# DCDC-12V5V1A.net
KiCad netlist of a schematic drawn in EAGLE
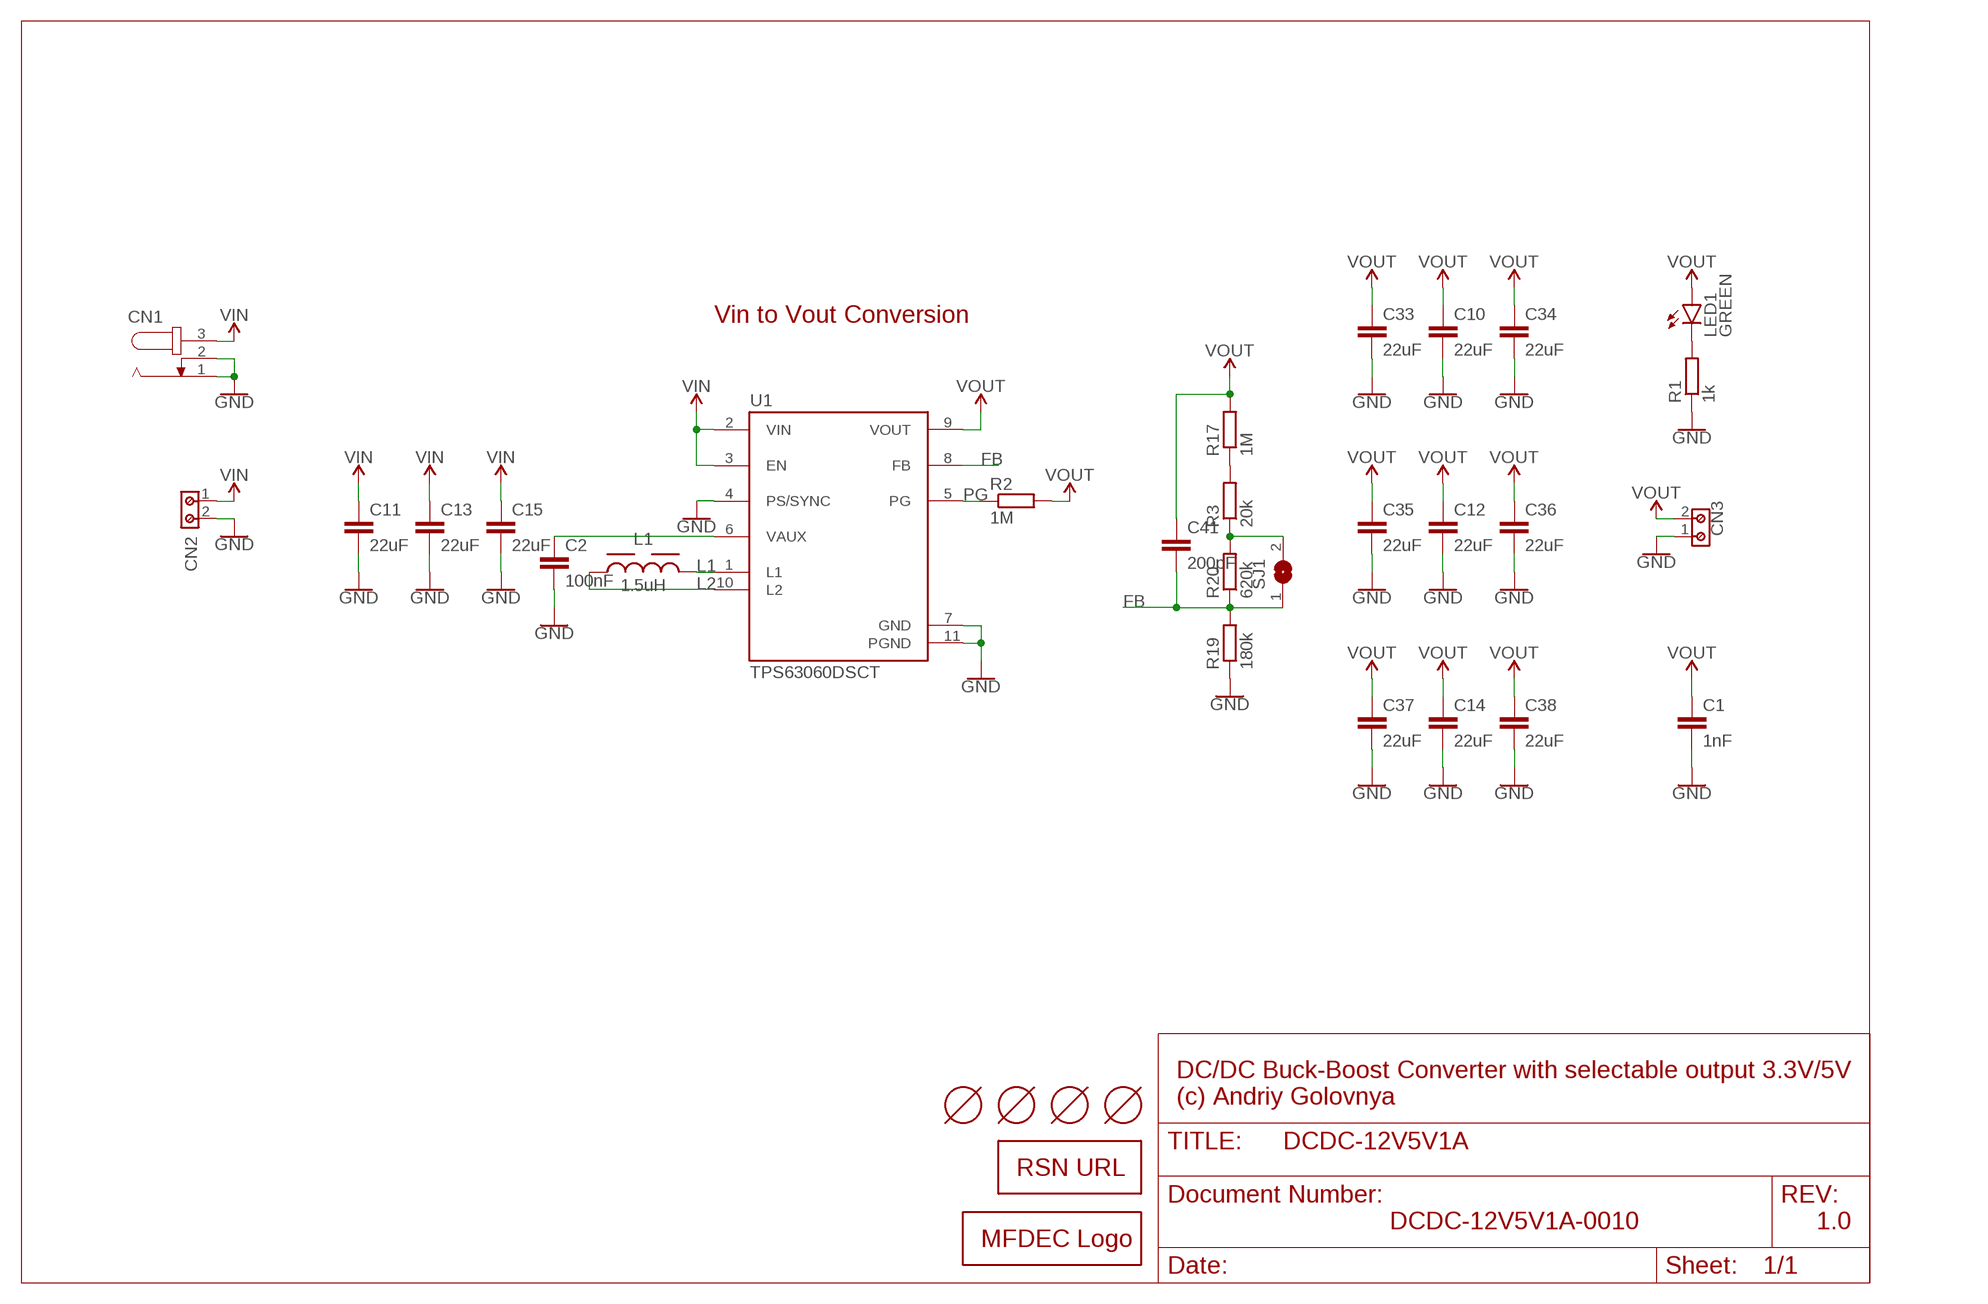
[diagram p0: schematic, sheet 1]

(export (version "E")
  (design (tool "Eeschema 10.0.6"))
  (components
    (comp (ref "C1")
      (value "1nF")
      (footprint "eagle-import:C0603K")
      (libsource (lib "eagle-import") (part "C-EUC0603K"))
    )
    (comp (ref "C2")
      (value "100nF")
      (footprint "eagle-import:C0603K")
      (libsource (lib "eagle-import") (part "C-EUC0603K"))
    )
    (comp (ref "C10")
      (value "22uF")
      (footprint "eagle-import:C0805K")
      (libsource (lib "eagle-import") (part "C-EUC0805K"))
    )
    (comp (ref "C11")
      (value "22uF")
      (footprint "eagle-import:C0805K")
      (libsource (lib "eagle-import") (part "C-EUC0805K"))
    )
    (comp (ref "C12")
      (value "22uF")
      (footprint "eagle-import:C0805K")
      (libsource (lib "eagle-import") (part "C-EUC0805K"))
    )
    (comp (ref "C13")
      (value "22uF")
      (footprint "eagle-import:C0805K")
      (libsource (lib "eagle-import") (part "C-EUC0805K"))
    )
    (comp (ref "C14")
      (value "22uF")
      (footprint "eagle-import:C0805K")
      (libsource (lib "eagle-import") (part "C-EUC0805K"))
    )
    (comp (ref "C15")
      (value "22uF")
      (footprint "eagle-import:C0805K")
      (libsource (lib "eagle-import") (part "C-EUC0805K"))
    )
    (comp (ref "C33")
      (value "22uF")
      (footprint "eagle-import:C0805K")
      (libsource (lib "eagle-import") (part "C-EUC0805K"))
    )
    (comp (ref "C34")
      (value "22uF")
      (footprint "eagle-import:C0805K")
      (libsource (lib "eagle-import") (part "C-EUC0805K"))
    )
    (comp (ref "C35")
      (value "22uF")
      (footprint "eagle-import:C0805K")
      (libsource (lib "eagle-import") (part "C-EUC0805K"))
    )
    (comp (ref "C36")
      (value "22uF")
      (footprint "eagle-import:C0805K")
      (libsource (lib "eagle-import") (part "C-EUC0805K"))
    )
    (comp (ref "C37")
      (value "22uF")
      (footprint "eagle-import:C0805K")
      (libsource (lib "eagle-import") (part "C-EUC0805K"))
    )
    (comp (ref "C38")
      (value "22uF")
      (footprint "eagle-import:C0805K")
      (libsource (lib "eagle-import") (part "C-EUC0805K"))
    )
    (comp (ref "C41")
      (value "200pF")
      (footprint "eagle-import:C0603K")
      (libsource (lib "eagle-import") (part "C-EUC0603K"))
    )
    (comp (ref "CN1")
      (value "JACK-PLUG1")
      (footprint "eagle-import:SPC4078")
      (libsource (lib "eagle-import") (part "JACK-PLUG1"))
    )
    (comp (ref "CN2")
      (value "691213510002")
      (footprint "eagle-import:691213510002")
      (libsource (lib "eagle-import") (part "691213510002"))
    )
    (comp (ref "CN3")
      (value "691213510002")
      (footprint "eagle-import:691213510002")
      (libsource (lib "eagle-import") (part "691213510002"))
    )
    (comp (ref "HOLE1")
      (value "TOOLINGHOLE")
      (footprint "eagle-import:TOOLING-HOLE")
      (libsource (lib "eagle-import") (part "TOOLINGHOLE"))
    )
    (comp (ref "HOLE2")
      (value "TOOLINGHOLE")
      (footprint "eagle-import:TOOLING-HOLE")
      (libsource (lib "eagle-import") (part "TOOLINGHOLE"))
    )
    (comp (ref "HOLE3")
      (value "TOOLINGHOLE")
      (footprint "eagle-import:TOOLING-HOLE")
      (libsource (lib "eagle-import") (part "TOOLINGHOLE"))
    )
    (comp (ref "HOLE4")
      (value "TOOLINGHOLE")
      (footprint "eagle-import:TOOLING-HOLE")
      (libsource (lib "eagle-import") (part "TOOLINGHOLE"))
    )
    (comp (ref "L1")
      (value "1.5uH")
      (footprint "eagle-import:WE-LQS_4018")
      (libsource (lib "eagle-import") (part "WE-LQS_4018_74404042010"))
    )
    (comp (ref "LED1")
      (value "GREEN")
      (footprint "eagle-import:SML0603")
      (libsource (lib "eagle-import") (part "LEDSML0603"))
    )
    (comp (ref "LOGO1")
      (value "RSNURL_QR_8MM")
      (footprint "eagle-import:RSNURL_QR_8MM")
      (libsource (lib "eagle-import") (part "RSNURL_QR_8MM"))
    )
    (comp (ref "LOGO2")
      (value "MFDECLOGO_L_10MM")
      (footprint "eagle-import:MFDEC_L_10MM")
      (libsource (lib "eagle-import") (part "MFDECLOGO_L_10MM"))
    )
    (comp (ref "R1")
      (value "1k")
      (footprint "eagle-import:R0603")
      (libsource (lib "eagle-import") (part "R-EU_R0603"))
    )
    (comp (ref "R2")
      (value "1M")
      (footprint "eagle-import:R0603")
      (libsource (lib "eagle-import") (part "R-EU_R0603"))
    )
    (comp (ref "R3")
      (value "20k")
      (footprint "eagle-import:R0603")
      (libsource (lib "eagle-import") (part "R-EU_R0603"))
    )
    (comp (ref "R17")
      (value "1M")
      (footprint "eagle-import:R0603")
      (libsource (lib "eagle-import") (part "R-EU_R0603"))
    )
    (comp (ref "R19")
      (value "180k")
      (footprint "eagle-import:R0603")
      (libsource (lib "eagle-import") (part "R-EU_R0603"))
    )
    (comp (ref "R20")
      (value "620k")
      (footprint "eagle-import:R0603")
      (libsource (lib "eagle-import") (part "R-EU_R0603"))
    )
    (comp (ref "SJ1") (value "SJ") (footprint "eagle-import:SJ") (libsource (lib "eagle-import") (part "SJ")))
    (comp (ref "U1")
      (value "TPS63060DSCT")
      (footprint "eagle-import:CONV_TPS63060DSCT")
      (fields (field (name "MF") "Texas Instruments"))
      (libsource (lib "eagle-import") (part "TPS63060DSCT"))
    )
  )
  (nets
    (net (code "1") (name "/FB") (class "Default")
      (node (ref "C41") (pin "2") (pinfunction "2_2") (pintype "passive"))
      (node (ref "R19") (pin "2") (pinfunction "2_2") (pintype "passive"))
      (node (ref "R20") (pin "1") (pinfunction "1_1") (pintype "passive"))
      (node (ref "SJ1") (pin "1") (pinfunction "1_1") (pintype "passive"))
      (node (ref "U1") (pin "8") (pinfunction "FB_8") (pintype "input"))
    )
    (net (code "2") (name "/L1") (class "Default")
      (node (ref "L1") (pin "2") (pinfunction "2_2") (pintype "passive"))
      (node (ref "U1") (pin "1") (pinfunction "L1_1") (pintype "passive"))
    )
    (net (code "3") (name "/L2") (class "Default")
      (node (ref "L1") (pin "1") (pinfunction "1_1") (pintype "passive"))
      (node (ref "U1") (pin "10") (pinfunction "L2_10") (pintype "passive"))
    )
    (net (code "4") (name "/PG") (class "Default")
      (node (ref "R2") (pin "1") (pinfunction "1_1") (pintype "passive"))
      (node (ref "U1") (pin "5") (pinfunction "PG_5") (pintype "output"))
    )
    (net (code "5") (name "GND") (class "Default")
      (node (ref "C1") (pin "2") (pinfunction "2_2") (pintype "passive"))
      (node (ref "C10") (pin "2") (pinfunction "2_2") (pintype "passive"))
      (node (ref "C11") (pin "2") (pinfunction "2_2") (pintype "passive"))
      (node (ref "C12") (pin "2") (pinfunction "2_2") (pintype "passive"))
      (node (ref "C13") (pin "2") (pinfunction "2_2") (pintype "passive"))
      (node (ref "C14") (pin "2") (pinfunction "2_2") (pintype "passive"))
      (node (ref "C15") (pin "2") (pinfunction "2_2") (pintype "passive"))
      (node (ref "C2") (pin "2") (pinfunction "2_2") (pintype "passive"))
      (node (ref "C33") (pin "2") (pinfunction "2_2") (pintype "passive"))
      (node (ref "C34") (pin "2") (pinfunction "2_2") (pintype "passive"))
      (node (ref "C35") (pin "2") (pinfunction "2_2") (pintype "passive"))
      (node (ref "C36") (pin "2") (pinfunction "2_2") (pintype "passive"))
      (node (ref "C37") (pin "2") (pinfunction "2_2") (pintype "passive"))
      (node (ref "C38") (pin "2") (pinfunction "2_2") (pintype "passive"))
      (node (ref "CN1") (pin "1") (pinfunction "1_1") (pintype "passive"))
      (node (ref "CN1") (pin "2") (pinfunction "2_2") (pintype "passive"))
      (node (ref "CN2") (pin "2") (pinfunction "2_2") (pintype "passive"))
      (node (ref "CN3") (pin "1") (pinfunction "1_1") (pintype "passive"))
      (node (ref "R1") (pin "1") (pinfunction "1_1") (pintype "passive"))
      (node (ref "R19") (pin "1") (pinfunction "1_1") (pintype "passive"))
      (node (ref "U1") (pin "11") (pinfunction "PGND_11") (pintype "power_in"))
      (node (ref "U1") (pin "4") (pinfunction "PS/SYNC_4") (pintype "input"))
      (node (ref "U1") (pin "7") (pinfunction "GND_7") (pintype "power_in"))
    )
    (net (code "6") (name "Net-(LED1-PadC)") (class "Default")
      (node (ref "LED1") (pin "C") (pinfunction "C_C") (pintype "passive"))
      (node (ref "R1") (pin "2") (pinfunction "2_2") (pintype "passive"))
    )
    (net (code "7") (name "Net-(R17-Pad1)") (class "Default")
      (node (ref "R17") (pin "1") (pinfunction "1_1") (pintype "passive"))
      (node (ref "R3") (pin "2") (pinfunction "2_2") (pintype "passive"))
    )
    (net (code "8") (name "Net-(R20-Pad2)") (class "Default")
      (node (ref "R20") (pin "2") (pinfunction "2_2") (pintype "passive"))
      (node (ref "R3") (pin "1") (pinfunction "1_1") (pintype "passive"))
      (node (ref "SJ1") (pin "2") (pinfunction "2_2") (pintype "passive"))
    )
    (net (code "9") (name "Net-(U1-VAUX)") (class "Default")
      (node (ref "C2") (pin "1") (pinfunction "1_1") (pintype "passive"))
      (node (ref "U1") (pin "6") (pinfunction "VAUX_6") (pintype "passive"))
    )
    (net (code "10") (name "VIN") (class "Default")
      (node (ref "C11") (pin "1") (pinfunction "1_1") (pintype "passive"))
      (node (ref "C13") (pin "1") (pinfunction "1_1") (pintype "passive"))
      (node (ref "C15") (pin "1") (pinfunction "1_1") (pintype "passive"))
      (node (ref "CN1") (pin "3") (pinfunction "3_3") (pintype "passive"))
      (node (ref "CN2") (pin "1") (pinfunction "1_1") (pintype "passive"))
      (node (ref "U1") (pin "2") (pinfunction "VIN_2") (pintype "input"))
      (node (ref "U1") (pin "3") (pinfunction "EN_3") (pintype "input"))
    )
    (net (code "11") (name "VOUT") (class "Default")
      (node (ref "C1") (pin "1") (pinfunction "1_1") (pintype "passive"))
      (node (ref "C10") (pin "1") (pinfunction "1_1") (pintype "passive"))
      (node (ref "C12") (pin "1") (pinfunction "1_1") (pintype "passive"))
      (node (ref "C14") (pin "1") (pinfunction "1_1") (pintype "passive"))
      (node (ref "C33") (pin "1") (pinfunction "1_1") (pintype "passive"))
      (node (ref "C34") (pin "1") (pinfunction "1_1") (pintype "passive"))
      (node (ref "C35") (pin "1") (pinfunction "1_1") (pintype "passive"))
      (node (ref "C36") (pin "1") (pinfunction "1_1") (pintype "passive"))
      (node (ref "C37") (pin "1") (pinfunction "1_1") (pintype "passive"))
      (node (ref "C38") (pin "1") (pinfunction "1_1") (pintype "passive"))
      (node (ref "C41") (pin "1") (pinfunction "1_1") (pintype "passive"))
      (node (ref "CN3") (pin "2") (pinfunction "2_2") (pintype "passive"))
      (node (ref "LED1") (pin "A") (pinfunction "A_A") (pintype "passive"))
      (node (ref "R17") (pin "2") (pinfunction "2_2") (pintype "passive"))
      (node (ref "R2") (pin "2") (pinfunction "2_2") (pintype "passive"))
      (node (ref "U1") (pin "9") (pinfunction "VOUT_9") (pintype "output"))
    )
  )
)
